# 04-GPS.net
KiCad netlist of a schematic drawn in Altium Designer
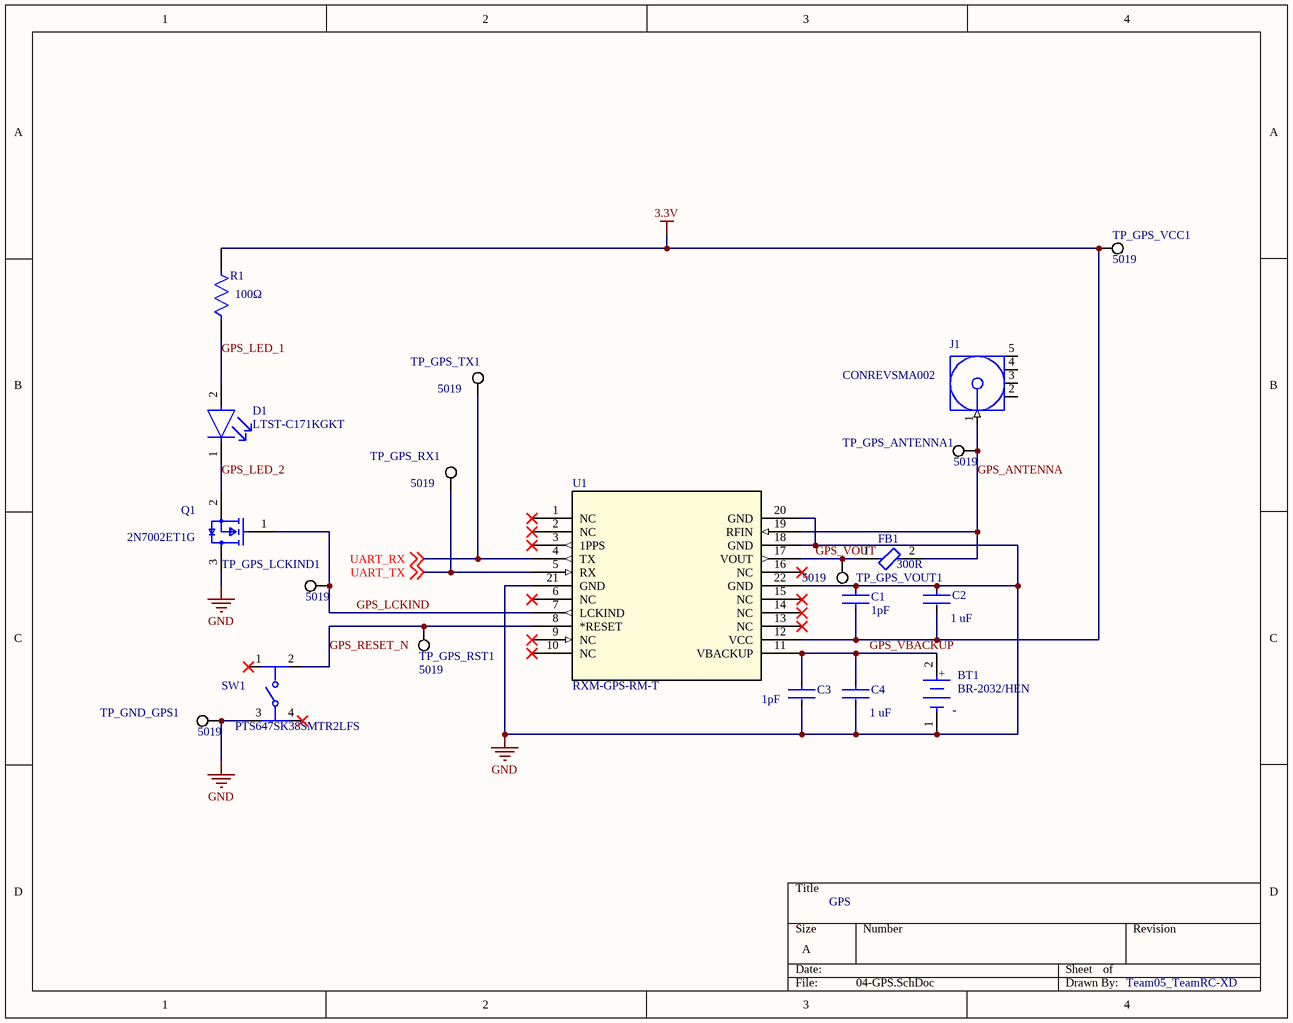
[diagram p0: 04-GPS.SchDoc]

(export (version "E")
  (design (tool "Eeschema 10.0.6"))
  (components
    (comp (ref "BT1")
      (value "BR-2032/HEN")
      (footprint "FP-BR-2032-HEN-MFG")
      (description "BATTERY LITHIUM 3V COIN 20MM")
      (fields
        (field (name "OCTOPART") "https://octopart.com/br-2032%2Fhen-panasonic-11763769")
        (field (name "MANUFACTURER") "Panasonic")
      )
      (libsource (lib "Altium Content Vault") (part "60d3b5b901a8747834971d0eb8cf3fd"))
    )
    (comp (ref "C1")
      (value "CC0805BRNPO9BN1R0")
      (footprint "FP-CC0805-0_1-0_7-IPC_B")
      (description "CAP CER 1PF 50V C0G/NPO 0805")
      (fields (field (name "CAPACITANCE") "1pF") (field (name "MANUFACTURER") "Yageo"))
      (libsource (lib "Altium Content Vault") (part "b4654b650e69147ec39a6b967a45e02"))
    )
    (comp (ref "C2")
      (value "1 uF")
      (footprint "FP-CC0805-0_85-MFG")
      (description "CAP CER 1UF 10V X7R 0805")
      (fields
        (field (name "MANUFACTURER") "Yageo")
        (field (name "OCTOPART") "https://octopart.com/cc0805kkx7r6bb105-yageo-42522859")
      )
      (libsource (lib "Altium Content Vault") (part "11868f565c42a9108669ba33697ecf6"))
    )
    (comp (ref "C3")
      (value "CC0805BRNPO9BN1R0")
      (footprint "FP-CC0805-0_1-0_7-IPC_B")
      (description "CAP CER 1PF 50V C0G/NPO 0805")
      (fields (field (name "CAPACITANCE") "1pF") (field (name "MANUFACTURER") "Yageo"))
      (libsource (lib "Altium Content Vault") (part "b4654b650e69147ec39a6b967a45e02"))
    )
    (comp (ref "C4")
      (value "1 uF")
      (footprint "FP-CC0805-0_85-MFG")
      (description "CAP CER 1UF 10V X7R 0805")
      (fields
        (field (name "MANUFACTURER") "Yageo")
        (field (name "OCTOPART") "https://octopart.com/cc0805kkx7r6bb105-yageo-42522859")
      )
      (libsource (lib "Altium Content Vault") (part "11868f565c42a9108669ba33697ecf6"))
    )
    (comp (ref "D1")
      (value "LTST-C171KGKT")
      (footprint "FP-LTST-C171KGKT-MFG")
      (description "LED GREEN CLEAR SMD")
      (fields (field (name "MANUFACTURER") "Vishay Lite-On"))
      (libsource (lib "Altium Content Vault") (part "8706943c75ba83719d021d2fdc84c58"))
    )
    (comp (ref "FB1")
      (value "MMZ1608D301BTA00")
      (footprint "FP-MMZ1608-0_8-MFG")
      (description "Signal Line Ferrite Bead 300Ω  @ 100MHz 300mA DCR 700mΩ SMD 0603")
      (fields (field (name "IMPEDANCE") "300R") (field (name "MANUFACTURER") "TDK"))
      (libsource (lib "Altium Content Vault") (part "5f30dd21d616792df468990f7003faa"))
    )
    (comp (ref "J1")
      (value "CONREVSMA002")
      (footprint "CON-REVSMA-RA")
      (description "RP-SMA Female Right Angle PCB Mount Connector, Thru-Hole")
      (fields (field (name "MANUFACTURER") "Linx") (field (name "MANUFACTURER PART NUMBER") "CONREVSMA002"))
      (libsource (lib "Altium Content Vault") (part "CN-1P-F-RF5"))
    )
    (comp (ref "Q1")
      (value "2N7002ET1G")
      (footprint "FP-318-08-IPC_A")
      (description "MOSFET N-CH 60V 260MA SOT-23")
      (fields
        (field (name "MANUFACTURER") "ON Semiconductor")
        (field (name "MANUFACTURER PART NUMBER") "2N7002ET1G")
      )
      (libsource (lib "Altium Content Vault") (part "a04dfd38ebfed9f67ad7f4c51a87371"))
    )
    (comp (ref "R1")
      (value "100Ω")
      (footprint "FP-RN732A-MFG")
      (description "SMD Chip Resistor, Thin Film, 100Ω, 100 V, 0805 [2012 Metric], 100 mW, 0.1%, RN73 Series")
      (fields
        (field (name "OCTOPART") "https://octopart.com/rn73c2a100rbtg-te+connectivity-41195811")
        (field (name "MANUFACTURER PART NUMBER") "RN73C2A100RBTG")
      )
      (libsource (lib "Altium Content Vault") (part "1029c3af85768c4190bb7ad29bc67b5"))
    )
    (comp (ref "SW1")
      (value "PTS647SK38SMTR2LFS")
      (footprint "FP-PTS647SK38SMTR2LFS-MFG")
      (description "TACT 4.5 X 4.5, 3.8 MM H, 2.5N,")
      (fields (field (name "MANUFACTURER") "ITT C&K"))
      (libsource (lib "Altium Content Vault") (part "1adf0dd01260c80cf25a44bfd6b99ba"))
    )
    (comp (ref "TP_GND_GPS1")
      (value "5019")
      (footprint "KSTN-5019_V")
      (description "Test Point, 1 Position SMD, RoHS, Tape and Reel")
      (fields (field (name "MANUFACTURER") "Keystone Electronics"))
      (libsource (lib "Altium Content Vault") (part "TESTPOINT_WHITE"))
    )
    (comp (ref "TP_GPS_ANTENNA1")
      (value "5019")
      (footprint "KSTN-5019_V")
      (description "Test Point, 1 Position SMD, RoHS, Tape and Reel")
      (fields (field (name "MANUFACTURER") "Keystone Electronics"))
      (libsource (lib "Altium Content Vault") (part "TESTPOINT_WHITE"))
    )
    (comp (ref "TP_GPS_LCKIND1")
      (value "5019")
      (footprint "KSTN-5019_V")
      (description "Test Point, 1 Position SMD, RoHS, Tape and Reel")
      (fields (field (name "MANUFACTURER") "Keystone Electronics"))
      (libsource (lib "Altium Content Vault") (part "TESTPOINT_WHITE"))
    )
    (comp (ref "TP_GPS_RST1")
      (value "5019")
      (footprint "KSTN-5019_V")
      (description "Test Point, 1 Position SMD, RoHS, Tape and Reel")
      (fields (field (name "MANUFACTURER") "Keystone Electronics"))
      (libsource (lib "Altium Content Vault") (part "TESTPOINT_WHITE"))
    )
    (comp (ref "TP_GPS_RX1")
      (value "5019")
      (footprint "KSTN-5019_V")
      (description "Test Point, 1 Position SMD, RoHS, Tape and Reel")
      (fields (field (name "MANUFACTURER") "Keystone Electronics"))
      (libsource (lib "Altium Content Vault") (part "TESTPOINT_WHITE"))
    )
    (comp (ref "TP_GPS_TX1")
      (value "5019")
      (footprint "KSTN-5019_V")
      (description "Test Point, 1 Position SMD, RoHS, Tape and Reel")
      (fields (field (name "MANUFACTURER") "Keystone Electronics"))
      (libsource (lib "Altium Content Vault") (part "TESTPOINT_WHITE"))
    )
    (comp (ref "TP_GPS_VCC1")
      (value "5019")
      (footprint "KSTN-5019_V")
      (description "Test Point, 1 Position SMD, RoHS, Tape and Reel")
      (fields (field (name "MANUFACTURER") "Keystone Electronics"))
      (libsource (lib "Altium Content Vault") (part "TESTPOINT_WHITE"))
    )
    (comp (ref "TP_GPS_VOUT1")
      (value "5019")
      (footprint "KSTN-5019_V")
      (description "Test Point, 1 Position SMD, RoHS, Tape and Reel")
      (fields (field (name "MANUFACTURER") "Keystone Electronics"))
      (libsource (lib "Altium Content Vault") (part "TESTPOINT_WHITE"))
    )
    (comp (ref "U1")
      (value "GPS")
      (footprint "RXM-GPS-RM-T_LNX")
      (description "RM Series GPS Receiver Module - Tape & Reel")
      (fields (field (name "MANUFACTURER") "Linx") (field (name "MANUFACTURER PART NUMBER") "RXM-GPS-RM-T"))
      (libsource (lib "ECE453-F22-Power") (part "GPS"))
    )
  )
  (nets
    (net (code "1") (name "/GPS_ANTENNA") (class "Default")
      (node (ref "FB1") (pin "2") (pinfunction "2_2") (pintype "passive"))
      (node (ref "J1") (pin "1") (pinfunction "Signal_1") (pintype "input"))
      (node (ref "TP_GPS_ANTENNA1") (pin "1") (pinfunction "1_1") (pintype "passive"))
      (node (ref "U1") (pin "19") (pinfunction "RFIN_19") (pintype "input"))
    )
    (net (code "2") (name "/GPS_LCKIND") (class "Default")
      (node (ref "Q1") (pin "1") (pinfunction "Gate_1") (pintype "passive"))
      (node (ref "TP_GPS_LCKIND1") (pin "1") (pinfunction "1_1") (pintype "passive"))
      (node (ref "U1") (pin "7") (pinfunction "LCKIND_7") (pintype "output"))
    )
    (net (code "3") (name "/GPS_LED_1") (class "Default")
      (node (ref "D1") (pin "2") (pinfunction "A_2") (pintype "passive"))
      (node (ref "R1") (pin "1") (pinfunction "1_1") (pintype "passive"))
    )
    (net (code "4") (name "/GPS_LED_2") (class "Default")
      (node (ref "D1") (pin "1") (pinfunction "C_1") (pintype "passive"))
      (node (ref "Q1") (pin "2") (pinfunction "Source_2") (pintype "passive"))
    )
    (net (code "5") (name "/GPS_RESET_N") (class "Default")
      (node (ref "SW1") (pin "2") (pinfunction "2_2") (pintype "passive"))
      (node (ref "TP_GPS_RST1") (pin "1") (pinfunction "1_1") (pintype "passive"))
      (node (ref "U1") (pin "8") (pinfunction "*RESET_8") (pintype "passive"))
    )
    (net (code "6") (name "/GPS_VBACKUP") (class "Default")
      (node (ref "BT1") (pin "2") (pinfunction "A_2") (pintype "passive"))
      (node (ref "C3") (pin "1") (pinfunction "1_1") (pintype "passive"))
      (node (ref "C4") (pin "1") (pinfunction "1_1") (pintype "passive"))
      (node (ref "U1") (pin "11") (pinfunction "VBACKUP_11") (pintype "power_in"))
    )
    (net (code "7") (name "/GPS_VOUT") (class "Default")
      (node (ref "FB1") (pin "1") (pinfunction "1_1") (pintype "passive"))
      (node (ref "TP_GPS_VOUT1") (pin "1") (pinfunction "1_1") (pintype "passive"))
      (node (ref "U1") (pin "17") (pinfunction "VOUT_17") (pintype "output"))
    )
    (net (code "8") (name "3.3V") (class "Default")
      (node (ref "C1") (pin "1") (pinfunction "1_1") (pintype "passive"))
      (node (ref "C2") (pin "2") (pinfunction "2_2") (pintype "passive"))
      (node (ref "R1") (pin "2") (pinfunction "2_2") (pintype "passive"))
      (node (ref "TP_GPS_VCC1") (pin "1") (pinfunction "1_1") (pintype "passive"))
      (node (ref "U1") (pin "12") (pinfunction "VCC_12") (pintype "power_in"))
    )
    (net (code "9") (name "GND") (class "Default")
      (node (ref "BT1") (pin "1") (pinfunction "C_1") (pintype "passive"))
      (node (ref "C1") (pin "2") (pinfunction "2_2") (pintype "passive"))
      (node (ref "C2") (pin "1") (pinfunction "1_1") (pintype "passive"))
      (node (ref "C3") (pin "2") (pinfunction "2_2") (pintype "passive"))
      (node (ref "C4") (pin "2") (pinfunction "2_2") (pintype "passive"))
      (node (ref "Q1") (pin "3") (pinfunction "Drain_3") (pintype "passive"))
      (node (ref "SW1") (pin "3") (pinfunction "3_3") (pintype "passive"))
      (node (ref "TP_GND_GPS1") (pin "1") (pinfunction "1_1") (pintype "passive"))
      (node (ref "U1") (pin "18") (pinfunction "GND_18") (pintype "passive"))
      (node (ref "U1") (pin "20") (pinfunction "GND_20") (pintype "passive"))
      (node (ref "U1") (pin "21") (pinfunction "GND_21") (pintype "passive"))
      (node (ref "U1") (pin "22") (pinfunction "GND_22") (pintype "passive"))
    )
    (net (code "10") (name "UART_RX") (class "Default")
      (node (ref "TP_GPS_TX1") (pin "1") (pinfunction "1_1") (pintype "passive"))
      (node (ref "U1") (pin "4") (pinfunction "TX_4") (pintype "output"))
    )
    (net (code "11") (name "UART_TX") (class "Default")
      (node (ref "TP_GPS_RX1") (pin "1") (pinfunction "1_1") (pintype "passive"))
      (node (ref "U1") (pin "5") (pinfunction "RX_5") (pintype "input"))
    )
    (net (code "12") (name "unconnected-(J1-GND-Pad2)") (class "Default")
      (node (ref "J1") (pin "2") (pinfunction "GND_2") (pintype "power_in"))
    )
    (net (code "13") (name "unconnected-(J1-GND-Pad3)") (class "Default")
      (node (ref "J1") (pin "3") (pinfunction "GND_3") (pintype "power_in"))
    )
    (net (code "14") (name "unconnected-(J1-GND-Pad4)") (class "Default")
      (node (ref "J1") (pin "4") (pinfunction "GND_4") (pintype "power_in"))
    )
    (net (code "15") (name "unconnected-(J1-GND-Pad5)") (class "Default")
      (node (ref "J1") (pin "5") (pinfunction "GND_5") (pintype "power_in"))
    )
    (net (code "16") (name "unconnected-(SW1-Pad1)") (class "Default")
      (node (ref "SW1") (pin "1") (pinfunction "1_1") (pintype "passive+no_connect"))
    )
    (net (code "17") (name "unconnected-(SW1-Pad4)") (class "Default")
      (node (ref "SW1") (pin "4") (pinfunction "4_4") (pintype "passive+no_connect"))
    )
    (net (code "18") (name "unconnected-(U1-1PPS-Pad3)") (class "Default")
      (node (ref "U1") (pin "3") (pinfunction "1PPS_3") (pintype "output+no_connect"))
    )
    (net (code "19") (name "unconnected-(U1-NC-Pad1)") (class "Default")
      (node (ref "U1") (pin "1") (pinfunction "NC_1") (pintype "passive+no_connect"))
    )
    (net (code "20") (name "unconnected-(U1-NC-Pad2)") (class "Default")
      (node (ref "U1") (pin "2") (pinfunction "NC_2") (pintype "passive+no_connect"))
    )
    (net (code "21") (name "unconnected-(U1-NC-Pad6)") (class "Default")
      (node (ref "U1") (pin "6") (pinfunction "NC_6") (pintype "passive+no_connect"))
    )
    (net (code "22") (name "unconnected-(U1-NC-Pad9)") (class "Default")
      (node (ref "U1") (pin "9") (pinfunction "NC_9") (pintype "input+no_connect"))
    )
    (net (code "23") (name "unconnected-(U1-NC-Pad10)") (class "Default")
      (node (ref "U1") (pin "10") (pinfunction "NC_10") (pintype "passive+no_connect"))
    )
    (net (code "24") (name "unconnected-(U1-NC-Pad13)") (class "Default")
      (node (ref "U1") (pin "13") (pinfunction "NC_13") (pintype "passive+no_connect"))
    )
    (net (code "25") (name "unconnected-(U1-NC-Pad14)") (class "Default")
      (node (ref "U1") (pin "14") (pinfunction "NC_14") (pintype "passive+no_connect"))
    )
    (net (code "26") (name "unconnected-(U1-NC-Pad15)") (class "Default")
      (node (ref "U1") (pin "15") (pinfunction "NC_15") (pintype "passive+no_connect"))
    )
    (net (code "27") (name "unconnected-(U1-NC-Pad16)") (class "Default")
      (node (ref "U1") (pin "16") (pinfunction "NC_16") (pintype "passive+no_connect"))
    )
  )
)
